# Auto2017.net
KiCad netlist of a schematic drawn in EAGLE
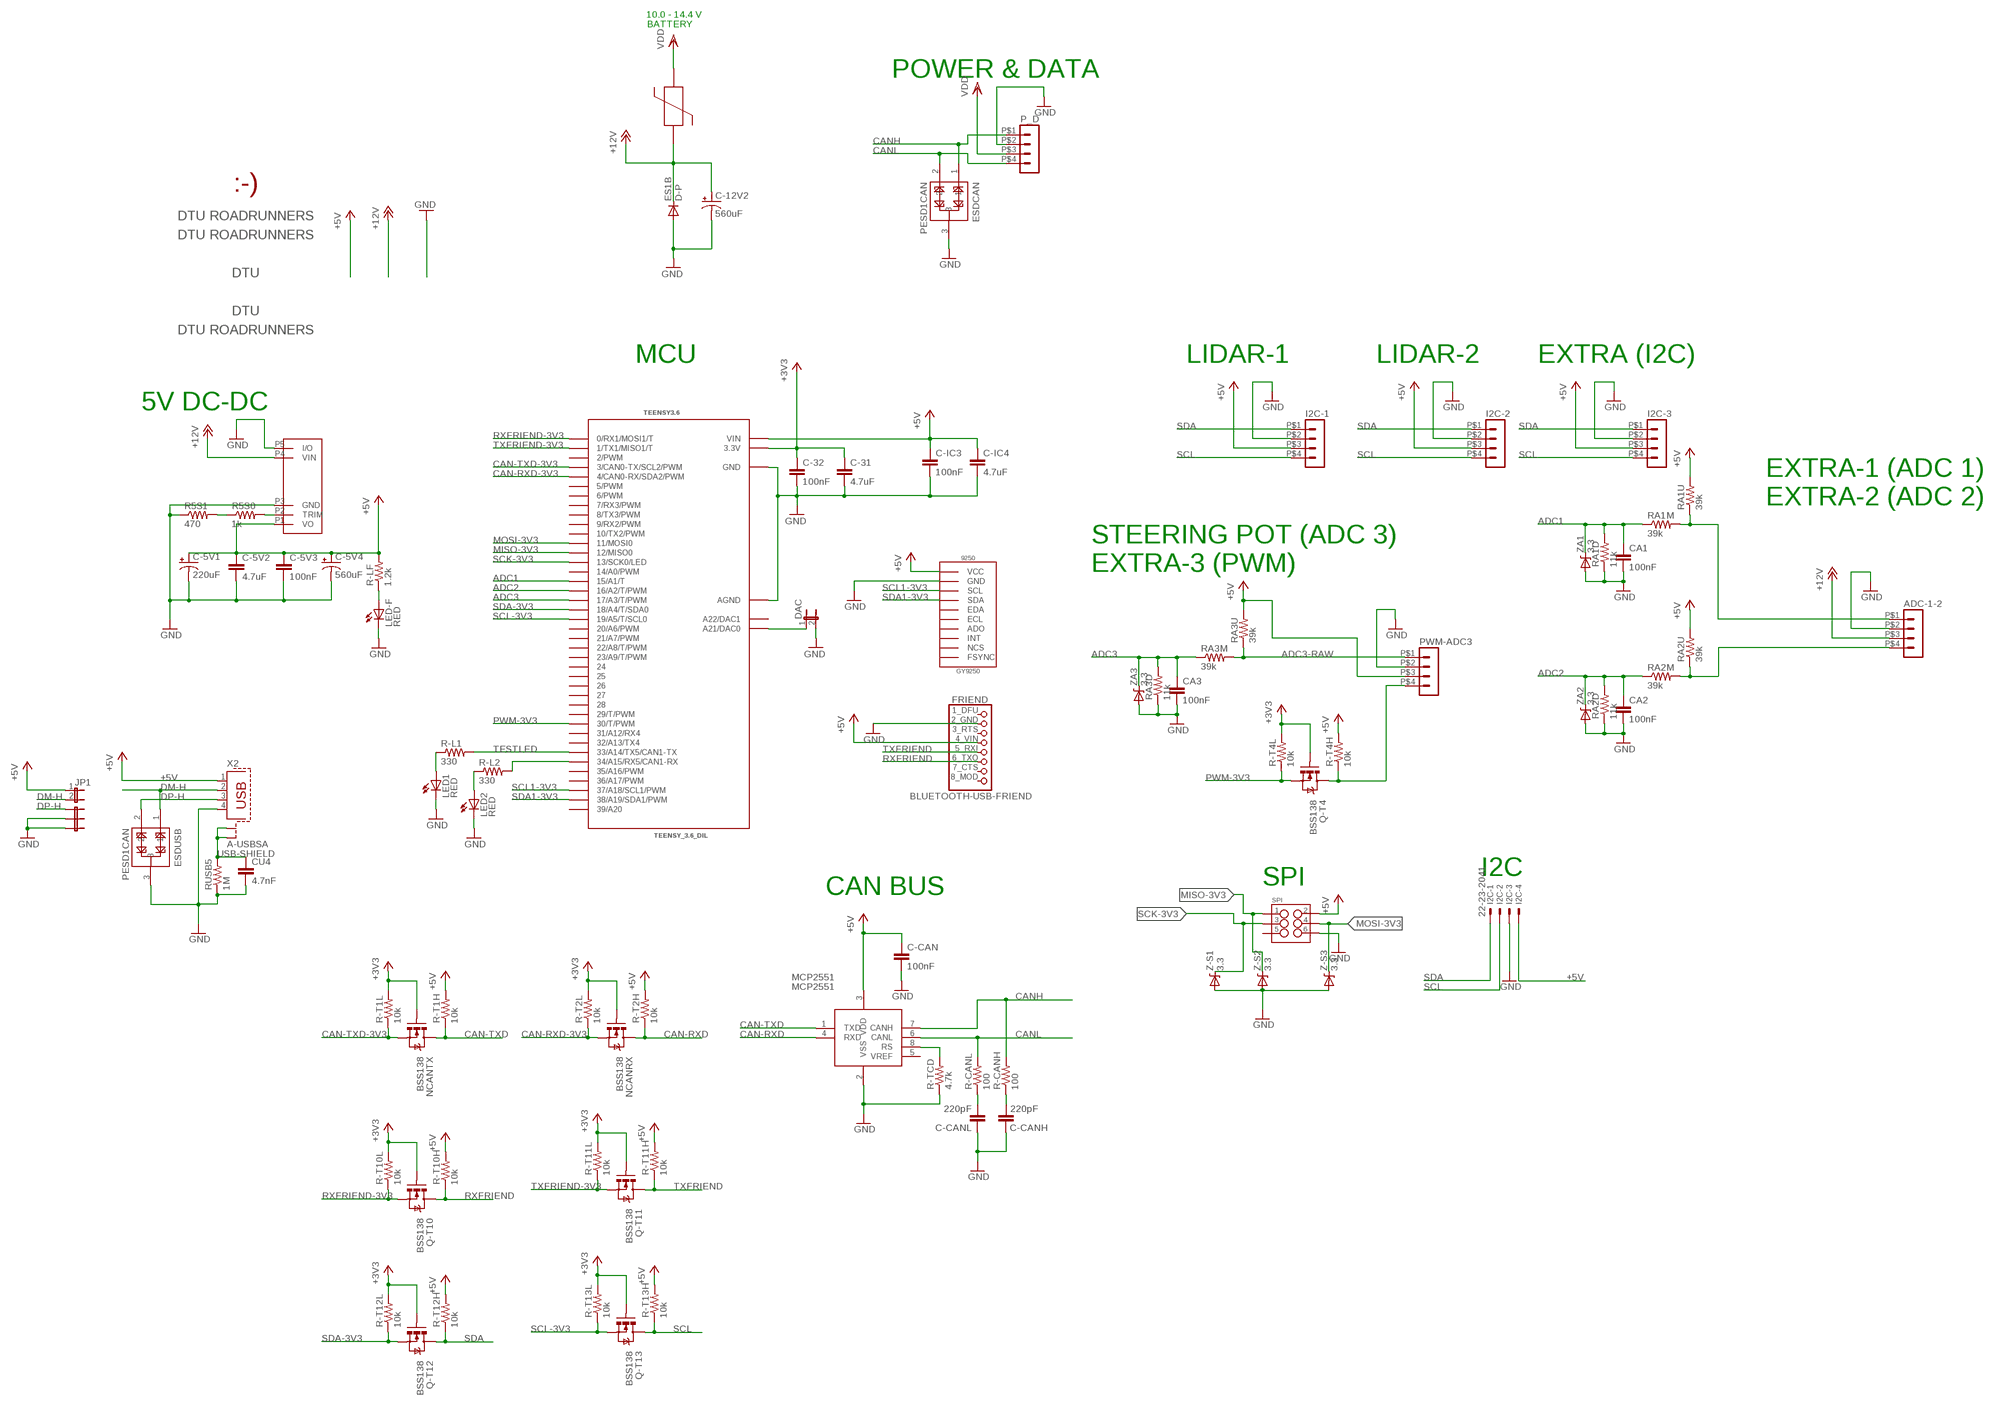
[diagram p0: schematic, sheet 1]

(export (version "E")
  (design (tool "Eeschema 10.0.6"))
  (components
    (comp (ref "9250")
      (value "GY9250")
      (footprint "eagle-import:GY9250")
      (libsource (lib "eagle-import") (part "GY9250"))
    )
    (comp (ref "ADC-1-2")
      (value "HEADER_POS4_43045-0401")
      (footprint "eagle-import:43045-0400")
      (libsource (lib "eagle-import") (part "HEADER_POS4_?43045-0401"))
    )
    (comp (ref "C-5V1")
      (value "220uF")
      (footprint "eagle-import:PANASONIC_D")
      (libsource (lib "eagle-import") (part "CPOL-USD"))
    )
    (comp (ref "C-5V2")
      (value "4.7uF")
      (footprint "eagle-import:1210")
      (libsource (lib "eagle-import") (part "CAP1210"))
    )
    (comp (ref "C-5V3")
      (value "100nF")
      (footprint "eagle-import:0805")
      (libsource (lib "eagle-import") (part "CAP0805"))
    )
    (comp (ref "C-5V4")
      (value "560uF")
      (footprint "eagle-import:PANASONIC_G")
      (libsource (lib "eagle-import") (part "CPOL-USG"))
    )
    (comp (ref "C-12V2")
      (value "560uF")
      (footprint "eagle-import:PANASONIC_G")
      (libsource (lib "eagle-import") (part "CPOL-USG"))
    )
    (comp (ref "C-31")
      (value "4.7uF")
      (footprint "eagle-import:1210")
      (libsource (lib "eagle-import") (part "CAP1210"))
    )
    (comp (ref "C-32")
      (value "100nF")
      (footprint "eagle-import:0805")
      (libsource (lib "eagle-import") (part "CAP0805"))
    )
    (comp (ref "C-CAN")
      (value "100nF")
      (footprint "eagle-import:0805")
      (libsource (lib "eagle-import") (part "CAP0805"))
    )
    (comp (ref "C-CANH")
      (value "220pF")
      (footprint "eagle-import:0805")
      (libsource (lib "eagle-import") (part "CAP0805"))
    )
    (comp (ref "C-CANL")
      (value "220pF")
      (footprint "eagle-import:0805")
      (libsource (lib "eagle-import") (part "CAP0805"))
    )
    (comp (ref "C-IC3")
      (value "100nF")
      (footprint "eagle-import:0805")
      (libsource (lib "eagle-import") (part "CAP0805"))
    )
    (comp (ref "C-IC4")
      (value "4.7uF")
      (footprint "eagle-import:1210")
      (libsource (lib "eagle-import") (part "CAP1210"))
    )
    (comp (ref "CA1")
      (value "100nF")
      (footprint "eagle-import:0805")
      (libsource (lib "eagle-import") (part "CAP0805"))
    )
    (comp (ref "CA2")
      (value "100nF")
      (footprint "eagle-import:0805")
      (libsource (lib "eagle-import") (part "CAP0805"))
    )
    (comp (ref "CA3")
      (value "100nF")
      (footprint "eagle-import:0805")
      (libsource (lib "eagle-import") (part "CAP0805"))
    )
    (comp (ref "CU4")
      (value "4.7nF")
      (footprint "eagle-import:0805")
      (libsource (lib "eagle-import") (part "CAP0805"))
    )
    (comp (ref "D-P")
      (value "ES1B")
      (footprint "eagle-import:SMA-DIODE")
      (libsource (lib "eagle-import") (part "DIODESMA"))
    )
    (comp (ref "DAC")
      (value "JUMPER-2PTH")
      (footprint "eagle-import:1X02")
      (libsource (lib "eagle-import") (part "JUMPER-2PTH"))
    )
    (comp (ref "ESDCAN")
      (value "PESD1CAN")
      (footprint "eagle-import:SOT23-3")
      (libsource (lib "eagle-import") (part "PESD1CAN"))
    )
    (comp (ref "ESDUSB")
      (value "PESD1CAN")
      (footprint "eagle-import:SOT23-3")
      (libsource (lib "eagle-import") (part "PESD1CAN"))
    )
    (comp (ref "FRIEND")
      (value "BLUETOOTH-USB-FRIEND")
      (footprint "eagle-import:1X08_ROUND_76")
      (libsource (lib "eagle-import") (part "BLUETOOTH-USB-FRIEND"))
    )
    (comp (ref "I2C")
      (value "22-23-2041")
      (footprint "eagle-import:22-23-2041")
      (fields (field (name "MF") "MOLEX"))
      (libsource (lib "eagle-import") (part "22-23-2041"))
    )
    (comp (ref "I2C-1")
      (value "HEADER_POS4_43045-0401")
      (footprint "eagle-import:43045-0400")
      (libsource (lib "eagle-import") (part "HEADER_POS4_?43045-0401"))
    )
    (comp (ref "I2C-2")
      (value "HEADER_POS4_43045-0401")
      (footprint "eagle-import:43045-0400")
      (libsource (lib "eagle-import") (part "HEADER_POS4_?43045-0401"))
    )
    (comp (ref "I2C-3")
      (value "HEADER_POS4_43045-0401")
      (footprint "eagle-import:43045-0400")
      (libsource (lib "eagle-import") (part "HEADER_POS4_?43045-0401"))
    )
    (comp (ref "JP1")
      (value "JUMPER-2PTH")
      (footprint "eagle-import:1X02")
      (libsource (lib "eagle-import") (part "JUMPER-2PTH"))
    )
    (comp (ref "JP3")
      (value "JUMPER-3PTH")
      (footprint "eagle-import:1X03")
      (libsource (lib "eagle-import") (part "JUMPER-3PTH"))
    )
    (comp (ref "LED-F")
      (value "RED")
      (footprint "eagle-import:LED-1206")
      (libsource (lib "eagle-import") (part "LED1206"))
    )
    (comp (ref "LED1")
      (value "RED")
      (footprint "eagle-import:LED-1206")
      (libsource (lib "eagle-import") (part "LED1206"))
    )
    (comp (ref "LED2")
      (value "RED")
      (footprint "eagle-import:LED-1206")
      (libsource (lib "eagle-import") (part "LED1206"))
    )
    (comp (ref "MAIN_FUSE")
      (value "SMF_OMNI-BLOK_FUSE_BLOCK")
      (footprint "eagle-import:SMF_OMNI-BLOK_FUSE_BLOCK")
      (libsource (lib "eagle-import") (part "SMF_OMNI-BLOK_FUSE_BLOCK"))
    )
    (comp (ref "MCP2551")
      (value "MCP2551")
      (footprint "eagle-import:SO-08M")
      (libsource (lib "eagle-import") (part "MCP2551"))
    )
    (comp (ref "NCANRX")
      (value "BSS138")
      (footprint "eagle-import:SOT23-3")
      (libsource (lib "eagle-import") (part "MOSFET-NCHANNELBSS123LT1G"))
    )
    (comp (ref "NCANTX")
      (value "BSS138")
      (footprint "eagle-import:SOT23-3")
      (libsource (lib "eagle-import") (part "MOSFET-NCHANNELBSS123LT1G"))
    )
    (comp (ref "PWM-ADC3")
      (value "HEADER_POS4_43045-0401")
      (footprint "eagle-import:43045-0400")
      (libsource (lib "eagle-import") (part "HEADER_POS4_?43045-0401"))
    )
    (comp (ref "P_D")
      (value "HEADER_POS4_43045-0401")
      (footprint "eagle-import:43045-0400")
      (libsource (lib "eagle-import") (part "HEADER_POS4_?43045-0401"))
    )
    (comp (ref "Q-T4")
      (value "BSS138")
      (footprint "eagle-import:SOT23-3")
      (libsource (lib "eagle-import") (part "MOSFET-NCHANNELBSS123LT1G"))
    )
    (comp (ref "Q-T10")
      (value "BSS138")
      (footprint "eagle-import:SOT23-3")
      (libsource (lib "eagle-import") (part "MOSFET-NCHANNELBSS123LT1G"))
    )
    (comp (ref "Q-T11")
      (value "BSS138")
      (footprint "eagle-import:SOT23-3")
      (libsource (lib "eagle-import") (part "MOSFET-NCHANNELBSS123LT1G"))
    )
    (comp (ref "Q-T12")
      (value "BSS138")
      (footprint "eagle-import:SOT23-3")
      (libsource (lib "eagle-import") (part "MOSFET-NCHANNELBSS123LT1G"))
    )
    (comp (ref "Q-T13")
      (value "BSS138")
      (footprint "eagle-import:SOT23-3")
      (libsource (lib "eagle-import") (part "MOSFET-NCHANNELBSS123LT1G"))
    )
    (comp (ref "R-CANH")
      (value "100")
      (footprint "eagle-import:0805")
      (libsource (lib "eagle-import") (part "RESISTOR0805-RES"))
    )
    (comp (ref "R-CANL")
      (value "100")
      (footprint "eagle-import:0805")
      (libsource (lib "eagle-import") (part "RESISTOR0805-RES"))
    )
    (comp (ref "R-L1")
      (value "330")
      (footprint "eagle-import:0805")
      (libsource (lib "eagle-import") (part "RESISTOR0805-RES"))
    )
    (comp (ref "R-L2")
      (value "330")
      (footprint "eagle-import:0805")
      (libsource (lib "eagle-import") (part "RESISTOR0805-RES"))
    )
    (comp (ref "R-LF")
      (value "1.2k")
      (footprint "eagle-import:0805")
      (libsource (lib "eagle-import") (part "RESISTOR0805-RES"))
    )
    (comp (ref "R-T1H")
      (value "10k")
      (footprint "eagle-import:0805")
      (libsource (lib "eagle-import") (part "RESISTOR0805-RES"))
    )
    (comp (ref "R-T1L")
      (value "10k")
      (footprint "eagle-import:0805")
      (libsource (lib "eagle-import") (part "RESISTOR0805-RES"))
    )
    (comp (ref "R-T2H")
      (value "10k")
      (footprint "eagle-import:0805")
      (libsource (lib "eagle-import") (part "RESISTOR0805-RES"))
    )
    (comp (ref "R-T2L")
      (value "10k")
      (footprint "eagle-import:0805")
      (libsource (lib "eagle-import") (part "RESISTOR0805-RES"))
    )
    (comp (ref "R-T4H")
      (value "10k")
      (footprint "eagle-import:0805")
      (libsource (lib "eagle-import") (part "RESISTOR0805-RES"))
    )
    (comp (ref "R-T4L")
      (value "10k")
      (footprint "eagle-import:0805")
      (libsource (lib "eagle-import") (part "RESISTOR0805-RES"))
    )
    (comp (ref "R-T10H")
      (value "10k")
      (footprint "eagle-import:0805")
      (libsource (lib "eagle-import") (part "RESISTOR0805-RES"))
    )
    (comp (ref "R-T10L")
      (value "10k")
      (footprint "eagle-import:0805")
      (libsource (lib "eagle-import") (part "RESISTOR0805-RES"))
    )
    (comp (ref "R-T11H")
      (value "10k")
      (footprint "eagle-import:0805")
      (libsource (lib "eagle-import") (part "RESISTOR0805-RES"))
    )
    (comp (ref "R-T11L")
      (value "10k")
      (footprint "eagle-import:0805")
      (libsource (lib "eagle-import") (part "RESISTOR0805-RES"))
    )
    (comp (ref "R-T12H")
      (value "10k")
      (footprint "eagle-import:0805")
      (libsource (lib "eagle-import") (part "RESISTOR0805-RES"))
    )
    (comp (ref "R-T12L")
      (value "10k")
      (footprint "eagle-import:0805")
      (libsource (lib "eagle-import") (part "RESISTOR0805-RES"))
    )
    (comp (ref "R-T13H")
      (value "10k")
      (footprint "eagle-import:0805")
      (libsource (lib "eagle-import") (part "RESISTOR0805-RES"))
    )
    (comp (ref "R-T13L")
      (value "10k")
      (footprint "eagle-import:0805")
      (libsource (lib "eagle-import") (part "RESISTOR0805-RES"))
    )
    (comp (ref "R-TCD")
      (value "4.7k")
      (footprint "eagle-import:0805")
      (libsource (lib "eagle-import") (part "RESISTOR0805-RES"))
    )
    (comp (ref "R5S0")
      (value "1k")
      (footprint "eagle-import:0805")
      (libsource (lib "eagle-import") (part "RESISTOR0805-RES"))
    )
    (comp (ref "R5S1")
      (value "470")
      (footprint "eagle-import:0805")
      (libsource (lib "eagle-import") (part "RESISTOR0805-RES"))
    )
    (comp (ref "RA1D")
      (value "11k")
      (footprint "eagle-import:0805")
      (libsource (lib "eagle-import") (part "RESISTOR0805-RES"))
    )
    (comp (ref "RA1M")
      (value "39k")
      (footprint "eagle-import:0805")
      (libsource (lib "eagle-import") (part "RESISTOR0805-RES"))
    )
    (comp (ref "RA1U")
      (value "39k")
      (footprint "eagle-import:0805")
      (libsource (lib "eagle-import") (part "RESISTOR0805-RES"))
    )
    (comp (ref "RA2D")
      (value "11k")
      (footprint "eagle-import:0805")
      (libsource (lib "eagle-import") (part "RESISTOR0805-RES"))
    )
    (comp (ref "RA2M")
      (value "39k")
      (footprint "eagle-import:0805")
      (libsource (lib "eagle-import") (part "RESISTOR0805-RES"))
    )
    (comp (ref "RA2U")
      (value "39k")
      (footprint "eagle-import:0805")
      (libsource (lib "eagle-import") (part "RESISTOR0805-RES"))
    )
    (comp (ref "RA3D")
      (value "11k")
      (footprint "eagle-import:0805")
      (libsource (lib "eagle-import") (part "RESISTOR0805-RES"))
    )
    (comp (ref "RA3M")
      (value "39k")
      (footprint "eagle-import:0805")
      (libsource (lib "eagle-import") (part "RESISTOR0805-RES"))
    )
    (comp (ref "RA3U")
      (value "39k")
      (footprint "eagle-import:0805")
      (libsource (lib "eagle-import") (part "RESISTOR0805-RES"))
    )
    (comp (ref "RUSB5")
      (value "1M")
      (footprint "eagle-import:0805")
      (libsource (lib "eagle-import") (part "RESISTOR0805-RES"))
    )
    (comp (ref "SPI")
      (value "M03X2POGO_PINS")
      (footprint "eagle-import:2X3_POGO")
      (libsource (lib "eagle-import") (part "M03X2POGO_PINS"))
    )
    (comp (ref "TEENSY3.6")
      (value "TEENSY_3.6_DIL")
      (footprint "eagle-import:TEENSY_3.6_DIL")
      (libsource (lib "eagle-import") (part "TEENSY_3.6_DIL"))
    )
    (comp (ref "U$1")
      (value "AXA003A0XZ")
      (footprint "eagle-import:SIP")
      (libsource (lib "eagle-import") (part "AXA003A0XZ"))
    )
    (comp (ref "U$3")
      (value "DTUMEDIUM-9MM")
      (footprint "eagle-import:DTU-MEDIUM-9MM")
      (libsource (lib "eagle-import") (part "DTUMEDIUM-9MM"))
    )
    (comp (ref "U$4")
      (value "ROADRUNNERSFULL")
      (footprint "eagle-import:ROADRUNNERS-FULL")
      (libsource (lib "eagle-import") (part "ROADRUNNERSFULL"))
    )
    (comp (ref "U$5")
      (value "ROADRUNNERSSMALL")
      (footprint "eagle-import:ROADRUNNERS-SMALL")
      (libsource (lib "eagle-import") (part "ROADRUNNERSSMALL"))
    )
    (comp (ref "U$6")
      (value "SMILEY")
      (footprint "eagle-import:SMILEY")
      (libsource (lib "eagle-import") (part "SMILEY"))
    )
    (comp (ref "U$8")
      (value "DTUSMALL")
      (footprint "eagle-import:DTU-SMALL-5MM")
      (libsource (lib "eagle-import") (part "DTUSMALL"))
    )
    (comp (ref "U$9")
      (value "ROADRUNNERSFULL")
      (footprint "eagle-import:ROADRUNNERS-FULL")
      (libsource (lib "eagle-import") (part "ROADRUNNERSFULL"))
    )
    (comp (ref "X2")
      (value "A-USBSA")
      (footprint "eagle-import:USB-A")
      (libsource (lib "eagle-import") (part "A-USBSA"))
    )
    (comp (ref "Z-S1")
      (value "3.3")
      (footprint "eagle-import:SOD123")
      (libsource (lib "eagle-import") (part "ZENER"))
    )
    (comp (ref "Z-S2")
      (value "3.3")
      (footprint "eagle-import:SOD123")
      (libsource (lib "eagle-import") (part "ZENER"))
    )
    (comp (ref "Z-S3")
      (value "3.3")
      (footprint "eagle-import:SOD123")
      (libsource (lib "eagle-import") (part "ZENER"))
    )
    (comp (ref "ZA1")
      (value "3.3")
      (footprint "eagle-import:SOD123")
      (libsource (lib "eagle-import") (part "ZENER"))
    )
    (comp (ref "ZA2")
      (value "3.3")
      (footprint "eagle-import:SOD123")
      (libsource (lib "eagle-import") (part "ZENER"))
    )
    (comp (ref "ZA3")
      (value "3.3")
      (footprint "eagle-import:SOD123")
      (libsource (lib "eagle-import") (part "ZENER"))
    )
  )
  (nets
    (net (code "1") (name "+3V3") (class "Default")
      (node (ref "C-31") (pin "1") (pinfunction "1_1") (pintype "passive"))
      (node (ref "C-32") (pin "1") (pinfunction "1_1") (pintype "passive"))
      (node (ref "NCANRX") (pin "1") (pinfunction "G_1") (pintype "passive"))
      (node (ref "NCANTX") (pin "1") (pinfunction "G_1") (pintype "passive"))
      (node (ref "Q-T10") (pin "1") (pinfunction "G_1") (pintype "passive"))
      (node (ref "Q-T11") (pin "1") (pinfunction "G_1") (pintype "passive"))
      (node (ref "Q-T12") (pin "1") (pinfunction "G_1") (pintype "passive"))
      (node (ref "Q-T13") (pin "1") (pinfunction "G_1") (pintype "passive"))
      (node (ref "Q-T4") (pin "1") (pinfunction "G_1") (pintype "passive"))
      (node (ref "R-T10L") (pin "2") (pinfunction "2_2") (pintype "passive"))
      (node (ref "R-T11L") (pin "2") (pinfunction "2_2") (pintype "passive"))
      (node (ref "R-T12L") (pin "2") (pinfunction "2_2") (pintype "passive"))
      (node (ref "R-T13L") (pin "2") (pinfunction "2_2") (pintype "passive"))
      (node (ref "R-T1L") (pin "2") (pinfunction "2_2") (pintype "passive"))
      (node (ref "R-T2L") (pin "2") (pinfunction "2_2") (pintype "passive"))
      (node (ref "R-T4L") (pin "2") (pinfunction "2_2") (pintype "passive"))
      (node (ref "TEENSY3.6") (pin "3.3V") (pinfunction "3.3V_3.3V") (pintype "power_in"))
      (node (ref "TEENSY3.6") (pin "3.3V3") (pinfunction "3.3V_3.3V3") (pintype "power_in"))
    )
    (net (code "2") (name "+5V") (class "Default")
      (node (ref "9250") (pin "P$VCC") (pinfunction "VCC_P$VCC") (pintype "bidirectional"))
      (node (ref "C-5V1") (pin "+") (pinfunction "+_+") (pintype "passive"))
      (node (ref "C-5V2") (pin "1") (pinfunction "1_1") (pintype "passive"))
      (node (ref "C-5V3") (pin "1") (pinfunction "1_1") (pintype "passive"))
      (node (ref "C-5V4") (pin "+") (pinfunction "+_+") (pintype "passive"))
      (node (ref "C-CAN") (pin "1") (pinfunction "1_1") (pintype "passive"))
      (node (ref "C-IC3") (pin "1") (pinfunction "1_1") (pintype "passive"))
      (node (ref "C-IC4") (pin "1") (pinfunction "1_1") (pintype "passive"))
      (node (ref "FRIEND") (pin "4_VIN") (pinfunction "4_4_VIN") (pintype "passive"))
      (node (ref "I2C") (pin "4") (pinfunction "S_4") (pintype "passive"))
      (node (ref "I2C-1") (pin "P$3") (pinfunction "3_P$3") (pintype "passive"))
      (node (ref "I2C-2") (pin "P$3") (pinfunction "3_P$3") (pintype "passive"))
      (node (ref "I2C-3") (pin "P$3") (pinfunction "3_P$3") (pintype "passive"))
      (node (ref "JP1") (pin "1") (pinfunction "1_1") (pintype "passive"))
      (node (ref "MCP2551") (pin "3") (pinfunction "VDD_3") (pintype "power_in"))
      (node (ref "PWM-ADC3") (pin "P$3") (pinfunction "3_P$3") (pintype "passive"))
      (node (ref "R-LF") (pin "2") (pinfunction "2_2") (pintype "passive"))
      (node (ref "R-T10H") (pin "2") (pinfunction "2_2") (pintype "passive"))
      (node (ref "R-T11H") (pin "2") (pinfunction "2_2") (pintype "passive"))
      (node (ref "R-T12H") (pin "2") (pinfunction "2_2") (pintype "passive"))
      (node (ref "R-T13H") (pin "2") (pinfunction "2_2") (pintype "passive"))
      (node (ref "R-T1H") (pin "2") (pinfunction "2_2") (pintype "passive"))
      (node (ref "R-T2H") (pin "2") (pinfunction "2_2") (pintype "passive"))
      (node (ref "R-T4H") (pin "2") (pinfunction "2_2") (pintype "passive"))
      (node (ref "RA1U") (pin "2") (pinfunction "2_2") (pintype "passive"))
      (node (ref "RA2U") (pin "2") (pinfunction "2_2") (pintype "passive"))
      (node (ref "RA3U") (pin "2") (pinfunction "2_2") (pintype "passive"))
      (node (ref "SPI") (pin "P$2") (pinfunction "2_P$2") (pintype "bidirectional"))
      (node (ref "TEENSY3.6") (pin "VIN") (pinfunction "VIN_VIN") (pintype "power_in"))
      (node (ref "U$1") (pin "P1") (pinfunction "VO_P1") (pintype "bidirectional"))
      (node (ref "X2") (pin "1") (pinfunction "1_1") (pintype "passive"))
    )
    (net (code "3") (name "+12V") (class "Default")
      (node (ref "ADC-1-2") (pin "P$3") (pinfunction "3_P$3") (pintype "passive"))
      (node (ref "C-12V2") (pin "+") (pinfunction "+_+") (pintype "passive"))
      (node (ref "D-P") (pin "C") (pinfunction "C_C") (pintype "passive"))
      (node (ref "MAIN_FUSE") (pin "PIN1") (pinfunction "PIN1_PIN1") (pintype "bidirectional"))
      (node (ref "U$1") (pin "P4") (pinfunction "VIN_P4") (pintype "bidirectional"))
    )
    (net (code "4") (name "/ADC1") (class "Default")
      (node (ref "CA1") (pin "1") (pinfunction "1_1") (pintype "passive"))
      (node (ref "RA1D") (pin "2") (pinfunction "2_2") (pintype "passive"))
      (node (ref "RA1M") (pin "1") (pinfunction "1_1") (pintype "passive"))
      (node (ref "TEENSY3.6") (pin "15/A1") (pinfunction "15/A1/T_15/A1") (pintype "bidirectional"))
      (node (ref "ZA1") (pin "C") (pinfunction "C_C") (pintype "passive"))
    )
    (net (code "5") (name "/ADC2") (class "Default")
      (node (ref "CA2") (pin "1") (pinfunction "1_1") (pintype "passive"))
      (node (ref "RA2D") (pin "2") (pinfunction "2_2") (pintype "passive"))
      (node (ref "RA2M") (pin "1") (pinfunction "1_1") (pintype "passive"))
      (node (ref "TEENSY3.6") (pin "16/A2") (pinfunction "16/A2/T/PWM_16/A2") (pintype "bidirectional"))
      (node (ref "ZA2") (pin "C") (pinfunction "C_C") (pintype "passive"))
    )
    (net (code "6") (name "/ADC3") (class "Default")
      (node (ref "CA3") (pin "1") (pinfunction "1_1") (pintype "passive"))
      (node (ref "RA3D") (pin "2") (pinfunction "2_2") (pintype "passive"))
      (node (ref "RA3M") (pin "1") (pinfunction "1_1") (pintype "passive"))
      (node (ref "TEENSY3.6") (pin "17/A3") (pinfunction "17/A3/T/PWM_17/A3") (pintype "bidirectional"))
      (node (ref "ZA3") (pin "C") (pinfunction "C_C") (pintype "passive"))
    )
    (net (code "7") (name "/ADC3-RAW") (class "Default")
      (node (ref "PWM-ADC3") (pin "P$1") (pinfunction "1_P$1") (pintype "passive"))
      (node (ref "RA3M") (pin "2") (pinfunction "2_2") (pintype "passive"))
      (node (ref "RA3U") (pin "1") (pinfunction "1_1") (pintype "passive"))
    )
    (net (code "8") (name "/CAN-RXD") (class "Default")
      (node (ref "MCP2551") (pin "4") (pinfunction "RXD_4") (pintype "bidirectional"))
      (node (ref "NCANRX") (pin "3") (pinfunction "D_3") (pintype "passive"))
      (node (ref "R-T2H") (pin "1") (pinfunction "1_1") (pintype "passive"))
    )
    (net (code "9") (name "/CAN-RXD-3V3") (class "Default")
      (node (ref "NCANRX") (pin "2") (pinfunction "S_2") (pintype "passive"))
      (node (ref "R-T2L") (pin "1") (pinfunction "1_1") (pintype "passive"))
      (node (ref "TEENSY3.6") (pin "4") (pinfunction "4/CAN0-RX/SDA2/PWM_4") (pintype "bidirectional"))
    )
    (net (code "10") (name "/CAN-TXD") (class "Default")
      (node (ref "MCP2551") (pin "1") (pinfunction "TXD_1") (pintype "bidirectional"))
      (node (ref "NCANTX") (pin "3") (pinfunction "D_3") (pintype "passive"))
      (node (ref "R-T1H") (pin "1") (pinfunction "1_1") (pintype "passive"))
    )
    (net (code "11") (name "/CAN-TXD-3V3") (class "Default")
      (node (ref "NCANTX") (pin "2") (pinfunction "S_2") (pintype "passive"))
      (node (ref "R-T1L") (pin "1") (pinfunction "1_1") (pintype "passive"))
      (node (ref "TEENSY3.6") (pin "3") (pinfunction "3/CAN0-TX/SCL2/PWM_3") (pintype "bidirectional"))
    )
    (net (code "12") (name "/CANH") (class "Default")
      (node (ref "ESDCAN") (pin "1") (pinfunction "1_1") (pintype "bidirectional"))
      (node (ref "MCP2551") (pin "7") (pinfunction "CANH_7") (pintype "bidirectional"))
      (node (ref "P_D") (pin "P$1") (pinfunction "1_P$1") (pintype "passive"))
      (node (ref "R-CANH") (pin "2") (pinfunction "2_2") (pintype "passive"))
    )
    (net (code "13") (name "/CANL") (class "Default")
      (node (ref "ESDCAN") (pin "2") (pinfunction "2_2") (pintype "bidirectional"))
      (node (ref "MCP2551") (pin "6") (pinfunction "CANL_6") (pintype "bidirectional"))
      (node (ref "P_D") (pin "P$4") (pinfunction "4_P$4") (pintype "passive"))
      (node (ref "R-CANL") (pin "2") (pinfunction "2_2") (pintype "passive"))
    )
    (net (code "14") (name "/DM-H") (class "Default")
      (node (ref "ESDUSB") (pin "1") (pinfunction "1_1") (pintype "bidirectional"))
      (node (ref "JP1") (pin "2") (pinfunction "2_2") (pintype "passive"))
      (node (ref "X2") (pin "2") (pinfunction "2_2") (pintype "passive"))
    )
    (net (code "15") (name "/DP-H") (class "Default")
      (node (ref "ESDUSB") (pin "2") (pinfunction "2_2") (pintype "bidirectional"))
      (node (ref "JP3") (pin "1") (pinfunction "1_1") (pintype "passive"))
      (node (ref "X2") (pin "3") (pinfunction "3_3") (pintype "passive"))
    )
    (net (code "16") (name "/PWM-3V3") (class "Default")
      (node (ref "Q-T4") (pin "2") (pinfunction "S_2") (pintype "passive"))
      (node (ref "R-T4L") (pin "1") (pinfunction "1_1") (pintype "passive"))
      (node (ref "TEENSY3.6") (pin "30") (pinfunction "30/T/PWM_30") (pintype "bidirectional"))
    )
    (net (code "17") (name "/RXFRIEND") (class "Default")
      (node (ref "FRIEND") (pin "6_TXO") (pinfunction "6_6_TXO") (pintype "passive"))
      (node (ref "Q-T10") (pin "3") (pinfunction "D_3") (pintype "passive"))
      (node (ref "R-T10H") (pin "1") (pinfunction "1_1") (pintype "passive"))
    )
    (net (code "18") (name "/RXFRIEND-3V3") (class "Default")
      (node (ref "Q-T10") (pin "2") (pinfunction "S_2") (pintype "passive"))
      (node (ref "R-T10L") (pin "1") (pinfunction "1_1") (pintype "passive"))
      (node (ref "TEENSY3.6") (pin "0") (pinfunction "0/RX1/MOSI1/T_0") (pintype "bidirectional"))
    )
    (net (code "19") (name "/SCL") (class "Default")
      (node (ref "I2C") (pin "2") (pinfunction "S_2") (pintype "passive"))
      (node (ref "I2C-1") (pin "P$4") (pinfunction "4_P$4") (pintype "passive"))
      (node (ref "I2C-2") (pin "P$4") (pinfunction "4_P$4") (pintype "passive"))
      (node (ref "I2C-3") (pin "P$4") (pinfunction "4_P$4") (pintype "passive"))
      (node (ref "Q-T13") (pin "3") (pinfunction "D_3") (pintype "passive"))
      (node (ref "R-T13H") (pin "1") (pinfunction "1_1") (pintype "passive"))
    )
    (net (code "20") (name "/SCL-3V3") (class "Default")
      (node (ref "Q-T13") (pin "2") (pinfunction "S_2") (pintype "passive"))
      (node (ref "R-T13L") (pin "1") (pinfunction "1_1") (pintype "passive"))
      (node (ref "TEENSY3.6") (pin "19/A5") (pinfunction "19/A5/T/SCL0_19/A5") (pintype "bidirectional"))
    )
    (net (code "21") (name "/SCL1-3V3") (class "Default")
      (node (ref "9250") (pin "P$SCL") (pinfunction "SCL_P$SCL") (pintype "bidirectional"))
      (node (ref "TEENSY3.6") (pin "37/A18") (pinfunction "37/A18/SCL1/PWM_37/A18") (pintype "bidirectional"))
    )
    (net (code "22") (name "/SDA") (class "Default")
      (node (ref "I2C") (pin "1") (pinfunction "S_1") (pintype "passive"))
      (node (ref "I2C-1") (pin "P$1") (pinfunction "1_P$1") (pintype "passive"))
      (node (ref "I2C-2") (pin "P$1") (pinfunction "1_P$1") (pintype "passive"))
      (node (ref "I2C-3") (pin "P$1") (pinfunction "1_P$1") (pintype "passive"))
      (node (ref "Q-T12") (pin "3") (pinfunction "D_3") (pintype "passive"))
      (node (ref "R-T12H") (pin "1") (pinfunction "1_1") (pintype "passive"))
    )
    (net (code "23") (name "/SDA-3V3") (class "Default")
      (node (ref "Q-T12") (pin "2") (pinfunction "S_2") (pintype "passive"))
      (node (ref "R-T12L") (pin "1") (pinfunction "1_1") (pintype "passive"))
      (node (ref "TEENSY3.6") (pin "18/A4") (pinfunction "18/A4/T/SDA0_18/A4") (pintype "bidirectional"))
    )
    (net (code "24") (name "/SDA1-3V3") (class "Default")
      (node (ref "9250") (pin "P$SDA") (pinfunction "SDA_P$SDA") (pintype "bidirectional"))
      (node (ref "TEENSY3.6") (pin "38/A19") (pinfunction "38/A19/SDA1/PWM_38/A19") (pintype "bidirectional"))
    )
    (net (code "25") (name "/TESTLED") (class "Default")
      (node (ref "R-L1") (pin "2") (pinfunction "2_2") (pintype "passive"))
      (node (ref "TEENSY3.6") (pin "33/A14") (pinfunction "33/A14/TX5/CAN1-TX_33/A14") (pintype "bidirectional"))
    )
    (net (code "26") (name "/TXFRIEND") (class "Default")
      (node (ref "FRIEND") (pin "5_RXI") (pinfunction "5_5_RXI") (pintype "passive"))
      (node (ref "Q-T11") (pin "3") (pinfunction "D_3") (pintype "passive"))
      (node (ref "R-T11H") (pin "1") (pinfunction "1_1") (pintype "passive"))
    )
    (net (code "27") (name "/TXFRIEND-3V3") (class "Default")
      (node (ref "Q-T11") (pin "2") (pinfunction "S_2") (pintype "passive"))
      (node (ref "R-T11L") (pin "1") (pinfunction "1_1") (pintype "passive"))
      (node (ref "TEENSY3.6") (pin "1") (pinfunction "1/TX1/MISO1/T_1") (pintype "bidirectional"))
    )
    (net (code "28") (name "/USB-SHIELD") (class "Default")
      (node (ref "CU4") (pin "1") (pinfunction "1_1") (pintype "passive"))
      (node (ref "RUSB5") (pin "2") (pinfunction "2_2") (pintype "passive"))
      (node (ref "X2") (pin "S1") (pinfunction "S1_S1") (pintype "passive"))
      (node (ref "X2") (pin "S2") (pinfunction "S2_S2") (pintype "passive"))
    )
    (net (code "29") (name "GND") (class "Default")
      (node (ref "9250") (pin "P$GND") (pinfunction "GND_P$GND") (pintype "bidirectional"))
      (node (ref "ADC-1-2") (pin "P$2") (pinfunction "2_P$2") (pintype "passive"))
      (node (ref "C-12V2") (pin "-") (pinfunction "-_-") (pintype "passive"))
      (node (ref "C-31") (pin "2") (pinfunction "2_2") (pintype "passive"))
      (node (ref "C-32") (pin "2") (pinfunction "2_2") (pintype "passive"))
      (node (ref "C-5V1") (pin "-") (pinfunction "-_-") (pintype "passive"))
      (node (ref "C-5V2") (pin "2") (pinfunction "2_2") (pintype "passive"))
      (node (ref "C-5V3") (pin "2") (pinfunction "2_2") (pintype "passive"))
      (node (ref "C-5V4") (pin "-") (pinfunction "-_-") (pintype "passive"))
      (node (ref "C-CAN") (pin "2") (pinfunction "2_2") (pintype "passive"))
      (node (ref "C-CANH") (pin "1") (pinfunction "1_1") (pintype "passive"))
      (node (ref "C-CANL") (pin "1") (pinfunction "1_1") (pintype "passive"))
      (node (ref "C-IC3") (pin "2") (pinfunction "2_2") (pintype "passive"))
      (node (ref "C-IC4") (pin "2") (pinfunction "2_2") (pintype "passive"))
      (node (ref "CA1") (pin "2") (pinfunction "2_2") (pintype "passive"))
      (node (ref "CA2") (pin "2") (pinfunction "2_2") (pintype "passive"))
      (node (ref "CA3") (pin "2") (pinfunction "2_2") (pintype "passive"))
      (node (ref "CU4") (pin "2") (pinfunction "2_2") (pintype "passive"))
      (node (ref "D-P") (pin "A") (pinfunction "A_A") (pintype "passive"))
      (node (ref "DAC") (pin "2") (pinfunction "2_2") (pintype "passive"))
      (node (ref "ESDCAN") (pin "3") (pinfunction "3_3") (pintype "bidirectional"))
      (node (ref "ESDUSB") (pin "3") (pinfunction "3_3") (pintype "bidirectional"))
      (node (ref "FRIEND") (pin "2_GND") (pinfunction "2_2_GND") (pintype "passive"))
      (node (ref "I2C") (pin "3") (pinfunction "S_3") (pintype "passive"))
      (node (ref "I2C-1") (pin "P$2") (pinfunction "2_P$2") (pintype "passive"))
      (node (ref "I2C-2") (pin "P$2") (pinfunction "2_P$2") (pintype "passive"))
      (node (ref "I2C-3") (pin "P$2") (pinfunction "2_P$2") (pintype "passive"))
      (node (ref "JP3") (pin "2") (pinfunction "2_2") (pintype "passive"))
      (node (ref "JP3") (pin "3") (pinfunction "3_3") (pintype "passive"))
      (node (ref "LED-F") (pin "C") (pinfunction "C_C") (pintype "passive"))
      (node (ref "LED1") (pin "C") (pinfunction "C_C") (pintype "passive"))
      (node (ref "LED2") (pin "C") (pinfunction "C_C") (pintype "passive"))
      (node (ref "MCP2551") (pin "2") (pinfunction "VSS_2") (pintype "power_in"))
      (node (ref "PWM-ADC3") (pin "P$2") (pinfunction "2_P$2") (pintype "passive"))
      (node (ref "P_D") (pin "P$2") (pinfunction "2_P$2") (pintype "passive"))
      (node (ref "R-TCD") (pin "1") (pinfunction "1_1") (pintype "passive"))
      (node (ref "R5S1") (pin "1") (pinfunction "1_1") (pintype "passive"))
      (node (ref "RA1D") (pin "1") (pinfunction "1_1") (pintype "passive"))
      (node (ref "RA2D") (pin "1") (pinfunction "1_1") (pintype "passive"))
      (node (ref "RA3D") (pin "1") (pinfunction "1_1") (pintype "passive"))
      (node (ref "RUSB5") (pin "1") (pinfunction "1_1") (pintype "passive"))
      (node (ref "SPI") (pin "P$6") (pinfunction "6_P$6") (pintype "bidirectional"))
      (node (ref "TEENSY3.6") (pin "AGND") (pinfunction "AGND_AGND") (pintype "power_in"))
      (node (ref "TEENSY3.6") (pin "GND") (pinfunction "GND_GND") (pintype "power_in"))
      (node (ref "TEENSY3.6") (pin "GND1") (pinfunction "GND_GND1") (pintype "power_in"))
      (node (ref "U$1") (pin "P3") (pinfunction "GND_P3") (pintype "bidirectional"))
      (node (ref "U$1") (pin "P5") (pinfunction "I/O_P5") (pintype "bidirectional"))
      (node (ref "X2") (pin "4") (pinfunction "4_4") (pintype "passive"))
      (node (ref "Z-S1") (pin "A") (pinfunction "A_A") (pintype "passive"))
      (node (ref "Z-S2") (pin "A") (pinfunction "A_A") (pintype "passive"))
      (node (ref "Z-S3") (pin "A") (pinfunction "A_A") (pintype "passive"))
      (node (ref "ZA1") (pin "A") (pinfunction "A_A") (pintype "passive"))
      (node (ref "ZA2") (pin "A") (pinfunction "A_A") (pintype "passive"))
      (node (ref "ZA3") (pin "A") (pinfunction "A_A") (pintype "passive"))
    )
    (net (code "30") (name "MISO-3V3") (class "Default")
      (node (ref "SPI") (pin "P$1") (pinfunction "1_P$1") (pintype "bidirectional"))
      (node (ref "TEENSY3.6") (pin "12") (pinfunction "12/MISO0_12") (pintype "bidirectional"))
      (node (ref "Z-S2") (pin "C") (pinfunction "C_C") (pintype "passive"))
    )
    (net (code "31") (name "MOSI-3V3") (class "Default")
      (node (ref "SPI") (pin "P$4") (pinfunction "4_P$4") (pintype "bidirectional"))
      (node (ref "TEENSY3.6") (pin "11") (pinfunction "11/MOSI0_11") (pintype "bidirectional"))
      (node (ref "Z-S3") (pin "C") (pinfunction "C_C") (pintype "passive"))
    )
    (net (code "32") (name "Net-(ADC-1-2-1)") (class "Default")
      (node (ref "ADC-1-2") (pin "P$1") (pinfunction "1_P$1") (pintype "passive"))
      (node (ref "RA1M") (pin "2") (pinfunction "2_2") (pintype "passive"))
      (node (ref "RA1U") (pin "1") (pinfunction "1_1") (pintype "passive"))
    )
    (net (code "33") (name "Net-(ADC-1-2-4)") (class "Default")
      (node (ref "ADC-1-2") (pin "P$4") (pinfunction "4_P$4") (pintype "passive"))
      (node (ref "RA2M") (pin "2") (pinfunction "2_2") (pintype "passive"))
      (node (ref "RA2U") (pin "1") (pinfunction "1_1") (pintype "passive"))
    )
    (net (code "34") (name "Net-(C-CANH-Pad2)") (class "Default")
      (node (ref "C-CANH") (pin "2") (pinfunction "2_2") (pintype "passive"))
      (node (ref "R-CANH") (pin "1") (pinfunction "1_1") (pintype "passive"))
    )
    (net (code "35") (name "Net-(C-CANL-Pad2)") (class "Default")
      (node (ref "C-CANL") (pin "2") (pinfunction "2_2") (pintype "passive"))
      (node (ref "R-CANL") (pin "1") (pinfunction "1_1") (pintype "passive"))
    )
    (net (code "36") (name "Net-(LED-F-PadA)") (class "Default")
      (node (ref "LED-F") (pin "A") (pinfunction "A_A") (pintype "passive"))
      (node (ref "R-LF") (pin "1") (pinfunction "1_1") (pintype "passive"))
    )
    (net (code "37") (name "Net-(LED1-PadA)") (class "Default")
      (node (ref "LED1") (pin "A") (pinfunction "A_A") (pintype "passive"))
      (node (ref "R-L1") (pin "1") (pinfunction "1_1") (pintype "passive"))
    )
    (net (code "38") (name "Net-(LED2-PadA)") (class "Default")
      (node (ref "LED2") (pin "A") (pinfunction "A_A") (pintype "passive"))
      (node (ref "R-L2") (pin "1") (pinfunction "1_1") (pintype "passive"))
    )
    (net (code "39") (name "Net-(MCP2551-RS)") (class "Default")
      (node (ref "MCP2551") (pin "8") (pinfunction "RS_8") (pintype "bidirectional"))
      (node (ref "R-TCD") (pin "2") (pinfunction "2_2") (pintype "passive"))
    )
    (net (code "40") (name "Net-(PWM-ADC3-4)") (class "Default")
      (node (ref "PWM-ADC3") (pin "P$4") (pinfunction "4_P$4") (pintype "passive"))
      (node (ref "Q-T4") (pin "3") (pinfunction "D_3") (pintype "passive"))
      (node (ref "R-T4H") (pin "1") (pinfunction "1_1") (pintype "passive"))
    )
    (net (code "41") (name "Net-(R5S0-Pad1)") (class "Default")
      (node (ref "R5S0") (pin "1") (pinfunction "1_1") (pintype "passive"))
      (node (ref "R5S1") (pin "2") (pinfunction "2_2") (pintype "passive"))
    )
    (net (code "42") (name "Net-(TEENSY3.6-34{slash}A15{slash}RX5{slash}CAN1-RX)") (class "Default")
      (node (ref "R-L2") (pin "2") (pinfunction "2_2") (pintype "passive"))
      (node (ref "TEENSY3.6") (pin "34/A15") (pinfunction "34/A15/RX5/CAN1-RX_34/A15") (pintype "bidirectional"))
    )
    (net (code "43") (name "Net-(TEENSY3.6-A21{slash}DAC0)") (class "Default")
      (node (ref "DAC") (pin "1") (pinfunction "1_1") (pintype "passive"))
      (node (ref "TEENSY3.6") (pin "A21") (pinfunction "A21/DAC0_A21") (pintype "bidirectional"))
    )
    (net (code "44") (name "Net-(U$1-TRIM)") (class "Default")
      (node (ref "R5S0") (pin "2") (pinfunction "2_2") (pintype "passive"))
      (node (ref "U$1") (pin "P2") (pinfunction "TRIM_P2") (pintype "bidirectional"))
    )
    (net (code "45") (name "SCK-3V3") (class "Default")
      (node (ref "SPI") (pin "P$3") (pinfunction "3_P$3") (pintype "bidirectional"))
      (node (ref "TEENSY3.6") (pin "13") (pinfunction "13/SCK0/LED_13") (pintype "bidirectional"))
      (node (ref "Z-S1") (pin "C") (pinfunction "C_C") (pintype "passive"))
    )
    (net (code "46") (name "VDD") (class "Default")
      (node (ref "MAIN_FUSE") (pin "PIN2") (pinfunction "PIN2_PIN2") (pintype "bidirectional"))
      (node (ref "P_D") (pin "P$3") (pinfunction "3_P$3") (pintype "passive"))
    )
    (net (code "47") (name "unconnected-(9250-ADO-PadP$ADO)") (class "Default")
      (node (ref "9250") (pin "P$ADO") (pinfunction "ADO_P$ADO") (pintype "bidirectional"))
    )
    (net (code "48") (name "unconnected-(9250-ECL-PadP$ECL)") (class "Default")
      (node (ref "9250") (pin "P$ECL") (pinfunction "ECL_P$ECL") (pintype "bidirectional"))
    )
    (net (code "49") (name "unconnected-(9250-EDA-PadP$EDA)") (class "Default")
      (node (ref "9250") (pin "P$EDA") (pinfunction "EDA_P$EDA") (pintype "bidirectional"))
    )
    (net (code "50") (name "unconnected-(9250-FSYNC-PadP$FSYNC)") (class "Default")
      (node (ref "9250") (pin "P$FSYNC") (pinfunction "FSYNC_P$FSYNC") (pintype "bidirectional"))
    )
    (net (code "51") (name "unconnected-(9250-INT-PadP$INT)") (class "Default")
      (node (ref "9250") (pin "P$INT") (pinfunction "INT_P$INT") (pintype "bidirectional"))
    )
    (net (code "52") (name "unconnected-(9250-NCS-PadP$NCS)") (class "Default")
      (node (ref "9250") (pin "P$NCS") (pinfunction "NCS_P$NCS") (pintype "bidirectional"))
    )
    (net (code "53") (name "unconnected-(FRIEND-1-Pad1_DFU)") (class "Default")
      (node (ref "FRIEND") (pin "1_DFU") (pinfunction "1_1_DFU") (pintype "passive"))
    )
    (net (code "54") (name "unconnected-(FRIEND-3-Pad3_RTS)") (class "Default")
      (node (ref "FRIEND") (pin "3_RTS") (pinfunction "3_3_RTS") (pintype "passive"))
    )
    (net (code "55") (name "unconnected-(FRIEND-7-Pad7_CTS)") (class "Default")
      (node (ref "FRIEND") (pin "7_CTS") (pinfunction "7_7_CTS") (pintype "passive"))
    )
    (net (code "56") (name "unconnected-(FRIEND-8-Pad8_MOD)") (class "Default")
      (node (ref "FRIEND") (pin "8_MOD") (pinfunction "8_8_MOD") (pintype "passive"))
    )
    (net (code "57") (name "unconnected-(MCP2551-VREF-Pad5)") (class "Default")
      (node (ref "MCP2551") (pin "5") (pinfunction "VREF_5") (pintype "bidirectional"))
    )
    (net (code "58") (name "unconnected-(SPI-5-PadP$5)") (class "Default")
      (node (ref "SPI") (pin "P$5") (pinfunction "5_P$5") (pintype "bidirectional"))
    )
    (net (code "59") (name "unconnected-(TEENSY3.6-2{slash}PWM-Pad2)") (class "Default")
      (node (ref "TEENSY3.6") (pin "2") (pinfunction "2/PWM_2") (pintype "bidirectional"))
    )
    (net (code "60") (name "unconnected-(TEENSY3.6-5{slash}PWM-Pad5)") (class "Default")
      (node (ref "TEENSY3.6") (pin "5") (pinfunction "5/PWM_5") (pintype "bidirectional"))
    )
    (net (code "61") (name "unconnected-(TEENSY3.6-6{slash}PWM-Pad6)") (class "Default")
      (node (ref "TEENSY3.6") (pin "6") (pinfunction "6/PWM_6") (pintype "bidirectional"))
    )
    (net (code "62") (name "unconnected-(TEENSY3.6-7{slash}RX3{slash}PWM-Pad7)") (class "Default")
      (node (ref "TEENSY3.6") (pin "7") (pinfunction "7/RX3/PWM_7") (pintype "bidirectional"))
    )
    (net (code "63") (name "unconnected-(TEENSY3.6-8{slash}TX3{slash}PWM-Pad8)") (class "Default")
      (node (ref "TEENSY3.6") (pin "8") (pinfunction "8/TX3/PWM_8") (pintype "bidirectional"))
    )
    (net (code "64") (name "unconnected-(TEENSY3.6-9{slash}RX2{slash}PWM-Pad9)") (class "Default")
      (node (ref "TEENSY3.6") (pin "9") (pinfunction "9/RX2/PWM_9") (pintype "bidirectional"))
    )
    (net (code "65") (name "unconnected-(TEENSY3.6-10{slash}TX2{slash}PWM-Pad10)") (class "Default")
      (node (ref "TEENSY3.6") (pin "10") (pinfunction "10/TX2/PWM_10") (pintype "bidirectional"))
    )
    (net (code "66") (name "unconnected-(TEENSY3.6-14{slash}A0{slash}PWM-Pad14{slash}A0)") (class "Default")
      (node (ref "TEENSY3.6") (pin "14/A0") (pinfunction "14/A0/PWM_14/A0") (pintype "bidirectional"))
    )
    (net (code "67") (name "unconnected-(TEENSY3.6-20{slash}A6{slash}PWM-Pad20{slash}A6)") (class "Default")
      (node (ref "TEENSY3.6") (pin "20/A6") (pinfunction "20/A6/PWM_20/A6") (pintype "bidirectional"))
    )
    (net (code "68") (name "unconnected-(TEENSY3.6-21{slash}A7{slash}PWM-Pad21{slash}A7)") (class "Default")
      (node (ref "TEENSY3.6") (pin "21/A7") (pinfunction "21/A7/PWM_21/A7") (pintype "bidirectional"))
    )
    (net (code "69") (name "unconnected-(TEENSY3.6-22{slash}A8{slash}T{slash}PWM-Pad22{slash}A8)") (class "Default")
      (node (ref "TEENSY3.6") (pin "22/A8") (pinfunction "22/A8/T/PWM_22/A8") (pintype "bidirectional"))
    )
    (net (code "70") (name "unconnected-(TEENSY3.6-23{slash}A9{slash}T{slash}PWM-Pad23{slash}A9)") (class "Default")
      (node (ref "TEENSY3.6") (pin "23/A9") (pinfunction "23/A9/T/PWM_23/A9") (pintype "bidirectional"))
    )
    (net (code "71") (name "unconnected-(TEENSY3.6-29{slash}T{slash}PWM-Pad29)") (class "Default")
      (node (ref "TEENSY3.6") (pin "29") (pinfunction "29/T/PWM_29") (pintype "bidirectional"))
    )
    (net (code "72") (name "unconnected-(TEENSY3.6-31{slash}A12{slash}RX4-Pad31{slash}A12)") (class "Default")
      (node (ref "TEENSY3.6") (pin "31/A12") (pinfunction "31/A12/RX4_31/A12") (pintype "bidirectional"))
    )
    (net (code "73") (name "unconnected-(TEENSY3.6-32{slash}A13{slash}TX4-Pad32{slash}A13)") (class "Default")
      (node (ref "TEENSY3.6") (pin "32/A13") (pinfunction "32/A13/TX4_32/A13") (pintype "bidirectional"))
    )
    (net (code "74") (name "unconnected-(TEENSY3.6-35{slash}A16{slash}PWM-Pad35{slash}A16)") (class "Default")
      (node (ref "TEENSY3.6") (pin "35/A16") (pinfunction "35/A16/PWM_35/A16") (pintype "bidirectional"))
    )
    (net (code "75") (name "unconnected-(TEENSY3.6-36{slash}A17{slash}PWM-Pad36{slash}A17)") (class "Default")
      (node (ref "TEENSY3.6") (pin "36/A17") (pinfunction "36/A17/PWM_36/A17") (pintype "bidirectional"))
    )
    (net (code "76") (name "unconnected-(TEENSY3.6-A22{slash}DAC1-PadA22)") (class "Default")
      (node (ref "TEENSY3.6") (pin "A22") (pinfunction "A22/DAC1_A22") (pintype "bidirectional"))
    )
    (net (code "77") (name "unconnected-(TEENSY3.6-Pad24)") (class "Default")
      (node (ref "TEENSY3.6") (pin "24") (pinfunction "24_24") (pintype "bidirectional"))
    )
    (net (code "78") (name "unconnected-(TEENSY3.6-Pad25)") (class "Default")
      (node (ref "TEENSY3.6") (pin "25") (pinfunction "25_25") (pintype "bidirectional"))
    )
    (net (code "79") (name "unconnected-(TEENSY3.6-Pad26)") (class "Default")
      (node (ref "TEENSY3.6") (pin "26") (pinfunction "26_26") (pintype "bidirectional"))
    )
    (net (code "80") (name "unconnected-(TEENSY3.6-Pad27)") (class "Default")
      (node (ref "TEENSY3.6") (pin "27") (pinfunction "27_27") (pintype "bidirectional"))
    )
    (net (code "81") (name "unconnected-(TEENSY3.6-Pad28)") (class "Default")
      (node (ref "TEENSY3.6") (pin "28") (pinfunction "28_28") (pintype "bidirectional"))
    )
    (net (code "82") (name "unconnected-(TEENSY3.6-Pad39{slash}A20)") (class "Default")
      (node (ref "TEENSY3.6") (pin "39/A20") (pinfunction "39/A20_39/A20") (pintype "bidirectional"))
    )
  )
)
